# 44TSOPBreakout.net
KiCad netlist of a schematic drawn in Altium Designer
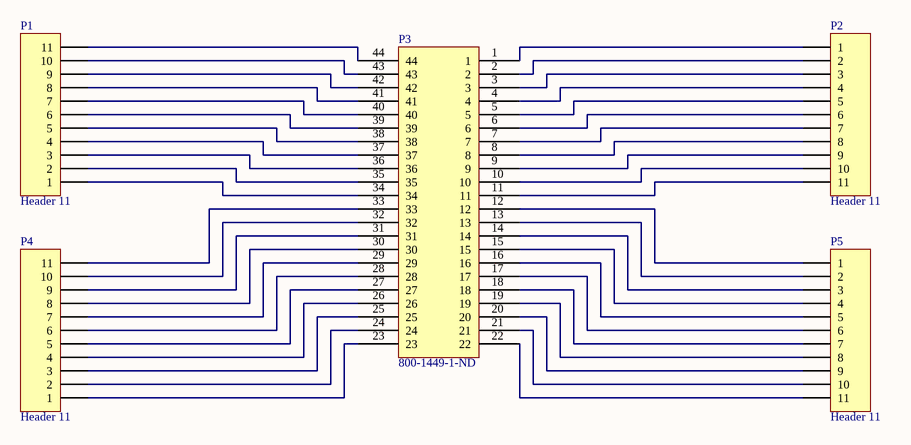
[diagram p0: 44TSOPBreakout.SchDoc]

(export (version "E")
  (design (tool "Eeschema 10.0.6"))
  (components
    (comp (ref "P1")
      (value "Header 11")
      (footprint "HDR1X11")
      (description "Header, 11-Pin")
      (fields (field (name "PUBLISHER") "Altium Limited"))
      (libsource (lib "Miscellaneous Connectors") (part "Header 11"))
    )
    (comp (ref "P2")
      (value "Header 11")
      (footprint "HDR1X11")
      (description "Header, 11-Pin")
      (fields (field (name "PUBLISHER") "Altium Limited"))
      (libsource (lib "") (part "Header 11_1"))
    )
    (comp (ref "P3")
      (value "71V016SA10PHG8")
      (footprint "TSOP80P1180X119-44N")
      (description "IC SRAM 1MBIT 10NS 44TSOP")
      (fields
        (field (name "MANUFACTURER") "IDT, Integrated Device Technology Inc")
        (field (name "SUPPLIER PART NUMBER 1") "800-1449-1-ND")
      )
      (libsource (lib "44TSOPBreakout") (part "71V016SA10PHG8"))
    )
    (comp (ref "P4")
      (value "Header 11")
      (footprint "HDR1X11")
      (description "Header, 11-Pin")
      (fields (field (name "PUBLISHER") "Altium Limited"))
      (libsource (lib "Miscellaneous Connectors") (part "Header 11"))
    )
    (comp (ref "P5")
      (value "Header 11")
      (footprint "HDR1X11")
      (description "Header, 11-Pin")
      (fields (field (name "PUBLISHER") "Altium Limited"))
      (libsource (lib "") (part "Header 11_1"))
    )
  )
  (nets
    (net (code "1") (name "Net-(P1-Pad1)") (class "Default")
      (node (ref "P1") (pin "1") (pinfunction "1_1") (pintype "passive"))
      (node (ref "P3") (pin "34") (pinfunction "34_34") (pintype "passive"))
    )
    (net (code "2") (name "Net-(P1-Pad2)") (class "Default")
      (node (ref "P1") (pin "2") (pinfunction "2_2") (pintype "passive"))
      (node (ref "P3") (pin "35") (pinfunction "35_35") (pintype "passive"))
    )
    (net (code "3") (name "Net-(P1-Pad3)") (class "Default")
      (node (ref "P1") (pin "3") (pinfunction "3_3") (pintype "passive"))
      (node (ref "P3") (pin "36") (pinfunction "36_36") (pintype "passive"))
    )
    (net (code "4") (name "Net-(P1-Pad4)") (class "Default")
      (node (ref "P1") (pin "4") (pinfunction "4_4") (pintype "passive"))
      (node (ref "P3") (pin "37") (pinfunction "37_37") (pintype "passive"))
    )
    (net (code "5") (name "Net-(P1-Pad5)") (class "Default")
      (node (ref "P1") (pin "5") (pinfunction "5_5") (pintype "passive"))
      (node (ref "P3") (pin "38") (pinfunction "38_38") (pintype "passive"))
    )
    (net (code "6") (name "Net-(P1-Pad6)") (class "Default")
      (node (ref "P1") (pin "6") (pinfunction "6_6") (pintype "passive"))
      (node (ref "P3") (pin "39") (pinfunction "39_39") (pintype "passive"))
    )
    (net (code "7") (name "Net-(P1-Pad7)") (class "Default")
      (node (ref "P1") (pin "7") (pinfunction "7_7") (pintype "passive"))
      (node (ref "P3") (pin "40") (pinfunction "40_40") (pintype "passive"))
    )
    (net (code "8") (name "Net-(P1-Pad8)") (class "Default")
      (node (ref "P1") (pin "8") (pinfunction "8_8") (pintype "passive"))
      (node (ref "P3") (pin "41") (pinfunction "41_41") (pintype "passive"))
    )
    (net (code "9") (name "Net-(P1-Pad9)") (class "Default")
      (node (ref "P1") (pin "9") (pinfunction "9_9") (pintype "passive"))
      (node (ref "P3") (pin "42") (pinfunction "42_42") (pintype "passive"))
    )
    (net (code "10") (name "Net-(P1-Pad10)") (class "Default")
      (node (ref "P1") (pin "10") (pinfunction "10_10") (pintype "passive"))
      (node (ref "P3") (pin "43") (pinfunction "43_43") (pintype "passive"))
    )
    (net (code "11") (name "Net-(P1-Pad11)") (class "Default")
      (node (ref "P1") (pin "11") (pinfunction "11_11") (pintype "passive"))
      (node (ref "P3") (pin "44") (pinfunction "44_44") (pintype "passive"))
    )
    (net (code "12") (name "Net-(P2-Pad1)") (class "Default")
      (node (ref "P2") (pin "1") (pinfunction "1_1") (pintype "passive"))
      (node (ref "P3") (pin "1") (pinfunction "1_1") (pintype "passive"))
    )
    (net (code "13") (name "Net-(P2-Pad2)") (class "Default")
      (node (ref "P2") (pin "2") (pinfunction "2_2") (pintype "passive"))
      (node (ref "P3") (pin "2") (pinfunction "2_2") (pintype "passive"))
    )
    (net (code "14") (name "Net-(P2-Pad3)") (class "Default")
      (node (ref "P2") (pin "3") (pinfunction "3_3") (pintype "passive"))
      (node (ref "P3") (pin "3") (pinfunction "3_3") (pintype "passive"))
    )
    (net (code "15") (name "Net-(P2-Pad4)") (class "Default")
      (node (ref "P2") (pin "4") (pinfunction "4_4") (pintype "passive"))
      (node (ref "P3") (pin "4") (pinfunction "4_4") (pintype "passive"))
    )
    (net (code "16") (name "Net-(P2-Pad5)") (class "Default")
      (node (ref "P2") (pin "5") (pinfunction "5_5") (pintype "passive"))
      (node (ref "P3") (pin "5") (pinfunction "5_5") (pintype "passive"))
    )
    (net (code "17") (name "Net-(P2-Pad6)") (class "Default")
      (node (ref "P2") (pin "6") (pinfunction "6_6") (pintype "passive"))
      (node (ref "P3") (pin "6") (pinfunction "6_6") (pintype "passive"))
    )
    (net (code "18") (name "Net-(P2-Pad7)") (class "Default")
      (node (ref "P2") (pin "7") (pinfunction "7_7") (pintype "passive"))
      (node (ref "P3") (pin "7") (pinfunction "7_7") (pintype "passive"))
    )
    (net (code "19") (name "Net-(P2-Pad8)") (class "Default")
      (node (ref "P2") (pin "8") (pinfunction "8_8") (pintype "passive"))
      (node (ref "P3") (pin "8") (pinfunction "8_8") (pintype "passive"))
    )
    (net (code "20") (name "Net-(P2-Pad9)") (class "Default")
      (node (ref "P2") (pin "9") (pinfunction "9_9") (pintype "passive"))
      (node (ref "P3") (pin "9") (pinfunction "9_9") (pintype "passive"))
    )
    (net (code "21") (name "Net-(P2-Pad10)") (class "Default")
      (node (ref "P2") (pin "10") (pinfunction "10_10") (pintype "passive"))
      (node (ref "P3") (pin "10") (pinfunction "10_10") (pintype "passive"))
    )
    (net (code "22") (name "Net-(P2-Pad11)") (class "Default")
      (node (ref "P2") (pin "11") (pinfunction "11_11") (pintype "passive"))
      (node (ref "P3") (pin "11") (pinfunction "11_11") (pintype "passive"))
    )
    (net (code "23") (name "Net-(P3-Pad12)") (class "Default")
      (node (ref "P3") (pin "12") (pinfunction "12_12") (pintype "passive"))
      (node (ref "P5") (pin "1") (pinfunction "1_1") (pintype "passive"))
    )
    (net (code "24") (name "Net-(P3-Pad13)") (class "Default")
      (node (ref "P3") (pin "13") (pinfunction "13_13") (pintype "passive"))
      (node (ref "P5") (pin "2") (pinfunction "2_2") (pintype "passive"))
    )
    (net (code "25") (name "Net-(P3-Pad14)") (class "Default")
      (node (ref "P3") (pin "14") (pinfunction "14_14") (pintype "passive"))
      (node (ref "P5") (pin "3") (pinfunction "3_3") (pintype "passive"))
    )
    (net (code "26") (name "Net-(P3-Pad15)") (class "Default")
      (node (ref "P3") (pin "15") (pinfunction "15_15") (pintype "passive"))
      (node (ref "P5") (pin "4") (pinfunction "4_4") (pintype "passive"))
    )
    (net (code "27") (name "Net-(P3-Pad16)") (class "Default")
      (node (ref "P3") (pin "16") (pinfunction "16_16") (pintype "passive"))
      (node (ref "P5") (pin "5") (pinfunction "5_5") (pintype "passive"))
    )
    (net (code "28") (name "Net-(P3-Pad17)") (class "Default")
      (node (ref "P3") (pin "17") (pinfunction "17_17") (pintype "passive"))
      (node (ref "P5") (pin "6") (pinfunction "6_6") (pintype "passive"))
    )
    (net (code "29") (name "Net-(P3-Pad18)") (class "Default")
      (node (ref "P3") (pin "18") (pinfunction "18_18") (pintype "passive"))
      (node (ref "P5") (pin "7") (pinfunction "7_7") (pintype "passive"))
    )
    (net (code "30") (name "Net-(P3-Pad19)") (class "Default")
      (node (ref "P3") (pin "19") (pinfunction "19_19") (pintype "passive"))
      (node (ref "P5") (pin "8") (pinfunction "8_8") (pintype "passive"))
    )
    (net (code "31") (name "Net-(P3-Pad20)") (class "Default")
      (node (ref "P3") (pin "20") (pinfunction "20_20") (pintype "passive"))
      (node (ref "P5") (pin "9") (pinfunction "9_9") (pintype "passive"))
    )
    (net (code "32") (name "Net-(P3-Pad21)") (class "Default")
      (node (ref "P3") (pin "21") (pinfunction "21_21") (pintype "passive"))
      (node (ref "P5") (pin "10") (pinfunction "10_10") (pintype "passive"))
    )
    (net (code "33") (name "Net-(P3-Pad22)") (class "Default")
      (node (ref "P3") (pin "22") (pinfunction "22_22") (pintype "passive"))
      (node (ref "P5") (pin "11") (pinfunction "11_11") (pintype "passive"))
    )
    (net (code "34") (name "Net-(P3-Pad23)") (class "Default")
      (node (ref "P3") (pin "23") (pinfunction "23_23") (pintype "passive"))
      (node (ref "P4") (pin "1") (pinfunction "1_1") (pintype "passive"))
    )
    (net (code "35") (name "Net-(P3-Pad24)") (class "Default")
      (node (ref "P3") (pin "24") (pinfunction "24_24") (pintype "passive"))
      (node (ref "P4") (pin "2") (pinfunction "2_2") (pintype "passive"))
    )
    (net (code "36") (name "Net-(P3-Pad25)") (class "Default")
      (node (ref "P3") (pin "25") (pinfunction "25_25") (pintype "passive"))
      (node (ref "P4") (pin "3") (pinfunction "3_3") (pintype "passive"))
    )
    (net (code "37") (name "Net-(P3-Pad26)") (class "Default")
      (node (ref "P3") (pin "26") (pinfunction "26_26") (pintype "passive"))
      (node (ref "P4") (pin "4") (pinfunction "4_4") (pintype "passive"))
    )
    (net (code "38") (name "Net-(P3-Pad27)") (class "Default")
      (node (ref "P3") (pin "27") (pinfunction "27_27") (pintype "passive"))
      (node (ref "P4") (pin "5") (pinfunction "5_5") (pintype "passive"))
    )
    (net (code "39") (name "Net-(P3-Pad28)") (class "Default")
      (node (ref "P3") (pin "28") (pinfunction "28_28") (pintype "passive"))
      (node (ref "P4") (pin "6") (pinfunction "6_6") (pintype "passive"))
    )
    (net (code "40") (name "Net-(P3-Pad29)") (class "Default")
      (node (ref "P3") (pin "29") (pinfunction "29_29") (pintype "passive"))
      (node (ref "P4") (pin "7") (pinfunction "7_7") (pintype "passive"))
    )
    (net (code "41") (name "Net-(P3-Pad30)") (class "Default")
      (node (ref "P3") (pin "30") (pinfunction "30_30") (pintype "passive"))
      (node (ref "P4") (pin "8") (pinfunction "8_8") (pintype "passive"))
    )
    (net (code "42") (name "Net-(P3-Pad31)") (class "Default")
      (node (ref "P3") (pin "31") (pinfunction "31_31") (pintype "passive"))
      (node (ref "P4") (pin "9") (pinfunction "9_9") (pintype "passive"))
    )
    (net (code "43") (name "Net-(P3-Pad32)") (class "Default")
      (node (ref "P3") (pin "32") (pinfunction "32_32") (pintype "passive"))
      (node (ref "P4") (pin "10") (pinfunction "10_10") (pintype "passive"))
    )
    (net (code "44") (name "Net-(P3-Pad33)") (class "Default")
      (node (ref "P3") (pin "33") (pinfunction "33_33") (pintype "passive"))
      (node (ref "P4") (pin "11") (pinfunction "11_11") (pintype "passive"))
    )
  )
)
